# 4ButtonBreakout.net
KiCad netlist of a schematic drawn in EAGLE
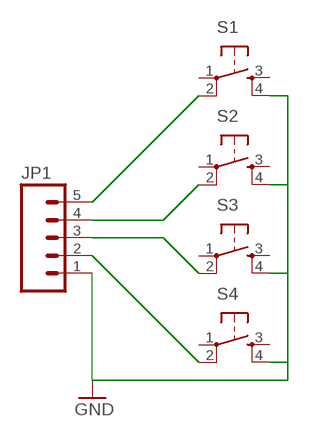
[diagram p0: schematic, sheet 1]

(export (version "E")
  (design (tool "Eeschema 10.0.6"))
  (components
    (comp (ref "JP1")
      (value "M05PTH")
      (footprint "eagle-import:1X05")
      (libsource (lib "eagle-import") (part "M05PTH"))
    )
    (comp (ref "S1")
      (value "TAC_SWITCH12MM")
      (footprint "eagle-import:B3F_10")
      (libsource (lib "eagle-import") (part "TAC_SWITCH12MM"))
    )
    (comp (ref "S2")
      (value "TAC_SWITCH12MM")
      (footprint "eagle-import:B3F_10")
      (libsource (lib "eagle-import") (part "TAC_SWITCH12MM"))
    )
    (comp (ref "S3")
      (value "TAC_SWITCH12MM")
      (footprint "eagle-import:B3F_10")
      (libsource (lib "eagle-import") (part "TAC_SWITCH12MM"))
    )
    (comp (ref "S4")
      (value "TAC_SWITCH12MM")
      (footprint "eagle-import:B3F_10")
      (libsource (lib "eagle-import") (part "TAC_SWITCH12MM"))
    )
  )
  (nets
    (net (code "1") (name "GND") (class "Default")
      (node (ref "JP1") (pin "1") (pinfunction "1_1") (pintype "passive"))
      (node (ref "S1") (pin "4") (pinfunction "4_4") (pintype "passive"))
      (node (ref "S2") (pin "4") (pinfunction "4_4") (pintype "passive"))
      (node (ref "S3") (pin "4") (pinfunction "4_4") (pintype "passive"))
      (node (ref "S4") (pin "4") (pinfunction "4_4") (pintype "passive"))
    )
    (net (code "2") (name "Net-(JP1-Pad2)") (class "Default")
      (node (ref "JP1") (pin "2") (pinfunction "2_2") (pintype "passive"))
      (node (ref "S4") (pin "2") (pinfunction "2_2") (pintype "passive"))
    )
    (net (code "3") (name "Net-(JP1-Pad3)") (class "Default")
      (node (ref "JP1") (pin "3") (pinfunction "3_3") (pintype "passive"))
      (node (ref "S3") (pin "2") (pinfunction "2_2") (pintype "passive"))
    )
    (net (code "4") (name "Net-(JP1-Pad4)") (class "Default")
      (node (ref "JP1") (pin "4") (pinfunction "4_4") (pintype "passive"))
      (node (ref "S2") (pin "2") (pinfunction "2_2") (pintype "passive"))
    )
    (net (code "5") (name "Net-(JP1-Pad5)") (class "Default")
      (node (ref "JP1") (pin "5") (pinfunction "5_5") (pintype "passive"))
      (node (ref "S1") (pin "2") (pinfunction "2_2") (pintype "passive"))
    )
    (net (code "6") (name "unconnected-(S1-Pad1)") (class "Default")
      (node (ref "S1") (pin "1") (pinfunction "1_1") (pintype "passive"))
    )
    (net (code "7") (name "unconnected-(S1-Pad3)") (class "Default")
      (node (ref "S1") (pin "3") (pinfunction "3_3") (pintype "passive"))
    )
    (net (code "8") (name "unconnected-(S2-Pad1)") (class "Default")
      (node (ref "S2") (pin "1") (pinfunction "1_1") (pintype "passive"))
    )
    (net (code "9") (name "unconnected-(S2-Pad3)") (class "Default")
      (node (ref "S2") (pin "3") (pinfunction "3_3") (pintype "passive"))
    )
    (net (code "10") (name "unconnected-(S3-Pad1)") (class "Default")
      (node (ref "S3") (pin "1") (pinfunction "1_1") (pintype "passive"))
    )
    (net (code "11") (name "unconnected-(S3-Pad3)") (class "Default")
      (node (ref "S3") (pin "3") (pinfunction "3_3") (pintype "passive"))
    )
    (net (code "12") (name "unconnected-(S4-Pad1)") (class "Default")
      (node (ref "S4") (pin "1") (pinfunction "1_1") (pintype "passive"))
    )
    (net (code "13") (name "unconnected-(S4-Pad3)") (class "Default")
      (node (ref "S4") (pin "3") (pinfunction "3_3") (pintype "passive"))
    )
  )
)
